# LVDS_BackLight.net
KiCad netlist of a schematic drawn in Altium Designer
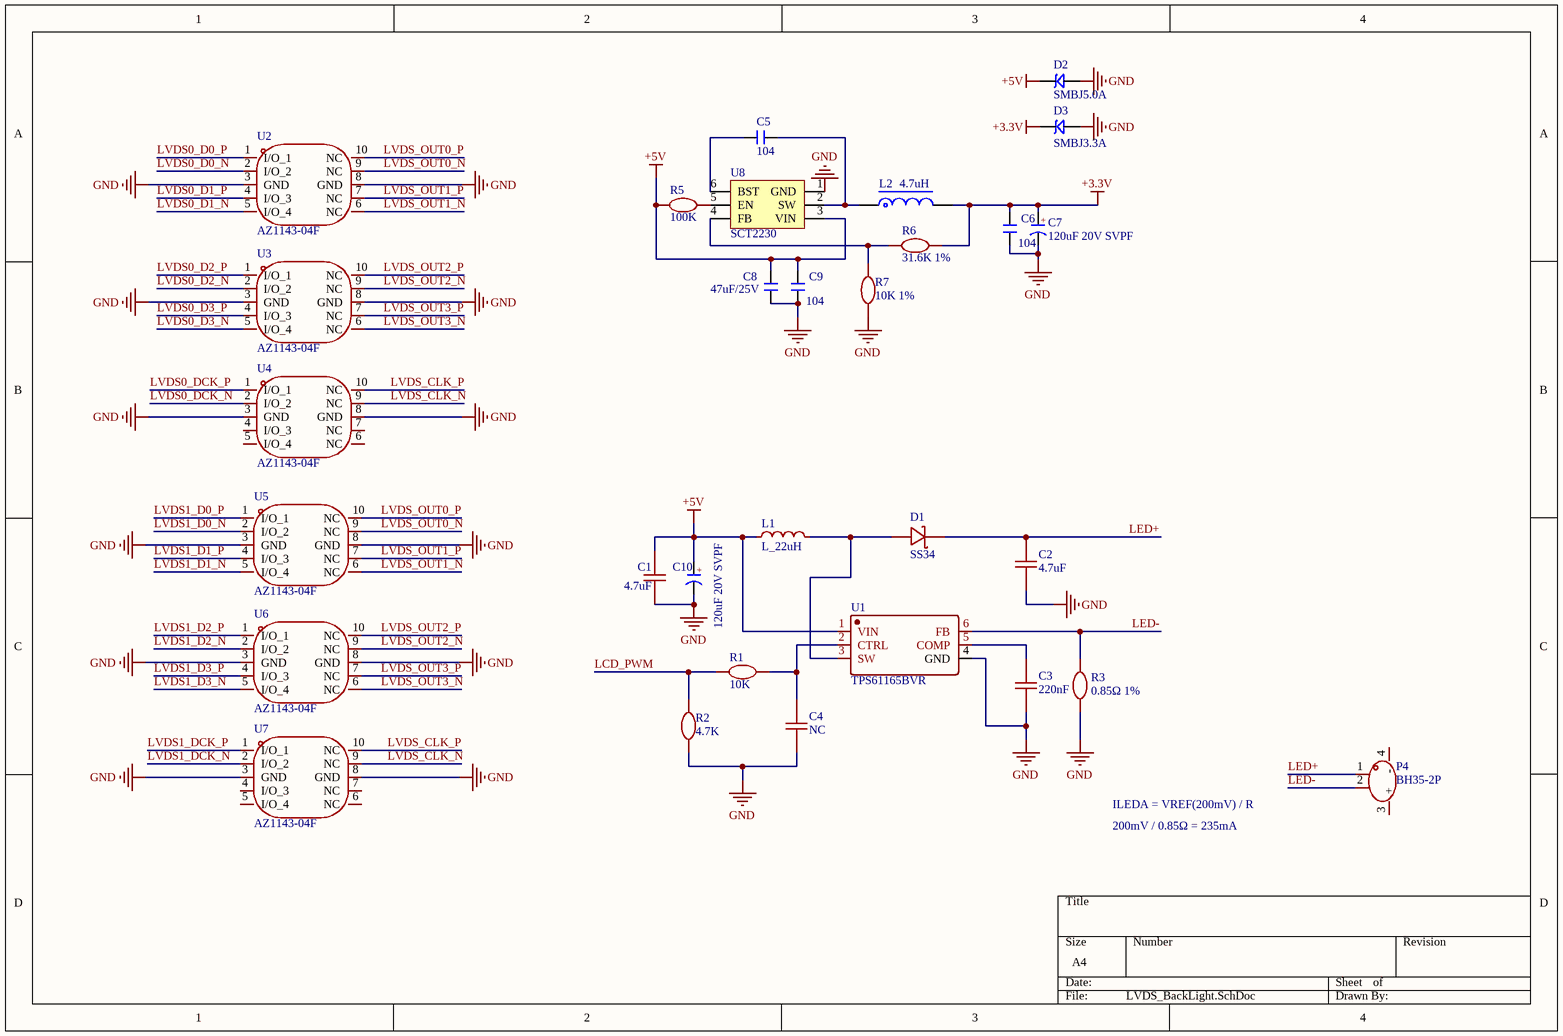
[diagram p0: LVDS_BackLight.SchDoc]

(export (version "E")
  (design (tool "Eeschema 10.0.6"))
  (components
    (comp (ref "C1") (value "4.7uF") (footprint "C0805") (libsource (lib "LVDS_Library") (part "C")))
    (comp (ref "C2") (value "4.7uF") (footprint "C0805") (libsource (lib "LVDS_Library") (part "C")))
    (comp (ref "C3") (value "220nF") (footprint "C0805") (libsource (lib "LVDS_Library") (part "C")))
    (comp (ref "C4") (value "NC") (footprint "C0805") (libsource (lib "LVDS_Library") (part "C")))
    (comp (ref "C5")
      (value "104")
      (footprint "C 0603")
      (description "无极性贴片电容")
      (fields (field (name "版权归属") "源创客"))
      (libsource (lib "ATK_DLRK3568_V1.5") (part "C"))
    )
    (comp (ref "C6")
      (value "104")
      (footprint "C 0603")
      (description "无极性贴片电容")
      (fields (field (name "版权归属") "源创客"))
      (libsource (lib "ATK_DLRK3568_V1.5") (part "C"))
    )
    (comp (ref "C7")
      (value "120uF 20V SVPF")
      (footprint "CM D(6.3*7.7)")
      (description "贴片电解电容")
      (fields (field (name "版权归属") "源创客"))
      (libsource (lib "ATK_DLRK3568_V1.5") (part "C-CM"))
    )
    (comp (ref "C8")
      (value "47uF/25V")
      (footprint "C 1206")
      (description "无极性贴片电容")
      (fields (field (name "版权归属") "源创客"))
      (libsource (lib "ATK_DLRK3568_V1.5") (part "C_1"))
    )
    (comp (ref "C9")
      (value "104")
      (footprint "C 0603")
      (description "无极性贴片电容")
      (fields (field (name "版权归属") "源创客"))
      (libsource (lib "ATK_DLRK3568_V1.5") (part "C"))
    )
    (comp (ref "C10")
      (value "120uF 20V SVPF")
      (footprint "CM D(6.3*7.7)")
      (description "贴片电解电容")
      (fields (field (name "版权归属") "源创客"))
      (libsource (lib "ATK_DLRK3568_V1.5") (part "C-CM"))
    )
    (comp (ref "D1")
      (value "SS34")
      (footprint "SS34_1")
      (description "肖特基二极管")
      (libsource (lib "LVDS_Library") (part "SS34"))
    )
    (comp (ref "D2")
      (value "SMBJ5.0A")
      (footprint "SMBJ")
      (description "TVS")
      (libsource (lib "ATK_DLRK3568_V1.5") (part "SMBJ"))
    )
    (comp (ref "D3")
      (value "SMBJ3.3A")
      (footprint "SMBJ")
      (description "TVS")
      (libsource (lib "ATK_DLRK3568_V1.5") (part "SMBJ_1"))
    )
    (comp (ref "L1") (value "L_22uH") (footprint "L_22uH") (libsource (lib "LVDS_Library") (part "L_22uH")))
    (comp (ref "L2")
      (value "4.7uH")
      (footprint "L-SMD-0420")
      (description "功率屏蔽电感")
      (fields (field (name "版权归属") "源创客"))
      (libsource (lib "ATK_DLRK3568_V1.5") (part "L-CDRH"))
    )
    (comp (ref "P4")
      (value "BH35-2P")
      (footprint "BH35-2P")
      (description "背光插头")
      (libsource (lib "LVDS_Library") (part "BH35-2P"))
    )
    (comp (ref "R1") (value "10K") (footprint "C0805") (libsource (lib "LVDS_Library") (part "R")))
    (comp (ref "R2") (value "4.7K") (footprint "C0805") (libsource (lib "LVDS_Library") (part "R")))
    (comp (ref "R3") (value "0.85Ω 1%") (footprint "C0805") (libsource (lib "LVDS_Library") (part "R")))
    (comp (ref "R5") (value "100K") (footprint "C0805") (libsource (lib "LVDS_Library") (part "R")))
    (comp (ref "R6") (value "31.6K 1%") (footprint "C0805") (libsource (lib "LVDS_Library") (part "R")))
    (comp (ref "R7") (value "10K 1%") (footprint "C0805") (libsource (lib "LVDS_Library") (part "R")))
    (comp (ref "U1")
      (value "TPS61165BVR")
      (footprint "TPS61165BVT")
      (description "TI背光芯片")
      (libsource (lib "LVDS_Library") (part "TPS61165BVR"))
    )
    (comp (ref "U2")
      (value "AZ1143-04F")
      (footprint "AZ1143-04F")
      (description "ESD 保护阵列")
      (libsource (lib "LVDS_Library") (part "AZ1143-04F"))
    )
    (comp (ref "U3")
      (value "AZ1143-04F")
      (footprint "AZ1143-04F")
      (description "ESD 保护阵列")
      (libsource (lib "LVDS_Library") (part "AZ1143-04F"))
    )
    (comp (ref "U4")
      (value "AZ1143-04F")
      (footprint "AZ1143-04F")
      (description "ESD 保护阵列")
      (libsource (lib "LVDS_Library") (part "AZ1143-04F"))
    )
    (comp (ref "U5")
      (value "AZ1143-04F")
      (footprint "AZ1143-04F")
      (description "ESD 保护阵列")
      (libsource (lib "LVDS_Library") (part "AZ1143-04F"))
    )
    (comp (ref "U6")
      (value "AZ1143-04F")
      (footprint "AZ1143-04F")
      (description "ESD 保护阵列")
      (libsource (lib "LVDS_Library") (part "AZ1143-04F"))
    )
    (comp (ref "U7")
      (value "AZ1143-04F")
      (footprint "AZ1143-04F")
      (description "ESD 保护阵列")
      (libsource (lib "LVDS_Library") (part "AZ1143-04F"))
    )
    (comp (ref "U8")
      (value "SCT2230")
      (footprint "SOT23-6N")
      (description "DC降压芯片")
      (libsource (lib "ATK_DLRK3568_V1.5") (part "DC JW5060T_6"))
    )
  )
  (nets
    (net (code "1") (name "+3.3V") (class "Default")
      (node (ref "C6") (pin "2") (pinfunction "2_2") (pintype "passive"))
      (node (ref "C7") (pin "1") (pinfunction "A_1") (pintype "passive"))
      (node (ref "D3") (pin "2") (pintype "passive"))
      (node (ref "L2") (pin "2") (pinfunction "2_2") (pintype "passive"))
      (node (ref "R6") (pin "1") (pinfunction "1_1") (pintype "passive"))
    )
    (net (code "2") (name "+5V") (class "Default")
      (node (ref "C1") (pin "2") (pinfunction "2_2") (pintype "passive"))
      (node (ref "C10") (pin "1") (pinfunction "A_1") (pintype "passive"))
      (node (ref "C8") (pin "2") (pinfunction "2_2") (pintype "passive"))
      (node (ref "C9") (pin "2") (pinfunction "2_2") (pintype "passive"))
      (node (ref "D2") (pin "2") (pintype "passive"))
      (node (ref "L1") (pin "1") (pinfunction "1_1") (pintype "passive"))
      (node (ref "R5") (pin "2") (pinfunction "2_2") (pintype "passive"))
      (node (ref "U1") (pin "1") (pinfunction "VIN_1") (pintype "passive"))
      (node (ref "U8") (pin "3") (pinfunction "VIN_3") (pintype "passive"))
    )
    (net (code "3") (name "/LCD_PWM") (class "Default")
      (node (ref "R1") (pin "2") (pinfunction "2_2") (pintype "passive"))
      (node (ref "R2") (pin "2") (pinfunction "2_2") (pintype "passive"))
    )
    (net (code "4") (name "/LED+") (class "Default")
      (node (ref "C2") (pin "2") (pinfunction "2_2") (pintype "passive"))
      (node (ref "D1") (pin "1") (pinfunction "C_1") (pintype "passive"))
      (node (ref "P4") (pin "1") (pinfunction "1_1") (pintype "passive"))
    )
    (net (code "5") (name "/LED-") (class "Default")
      (node (ref "P4") (pin "2") (pinfunction "2_2") (pintype "passive"))
      (node (ref "R3") (pin "2") (pinfunction "2_2") (pintype "passive"))
      (node (ref "U1") (pin "6") (pinfunction "FB_6") (pintype "passive"))
    )
    (net (code "6") (name "/LVDS0_D0_N") (class "Default")
      (node (ref "U2") (pin "2") (pinfunction "I/O_2_2") (pintype "passive"))
    )
    (net (code "7") (name "/LVDS0_D0_P") (class "Default")
      (node (ref "U2") (pin "1") (pinfunction "I/O_1_1") (pintype "passive"))
    )
    (net (code "8") (name "/LVDS0_D1_N") (class "Default")
      (node (ref "U2") (pin "5") (pinfunction "I/O_4_5") (pintype "passive"))
    )
    (net (code "9") (name "/LVDS0_D1_P") (class "Default")
      (node (ref "U2") (pin "4") (pinfunction "I/O_3_4") (pintype "passive"))
    )
    (net (code "10") (name "/LVDS0_D2_N") (class "Default")
      (node (ref "U3") (pin "2") (pinfunction "I/O_2_2") (pintype "passive"))
    )
    (net (code "11") (name "/LVDS0_D2_P") (class "Default")
      (node (ref "U3") (pin "1") (pinfunction "I/O_1_1") (pintype "passive"))
    )
    (net (code "12") (name "/LVDS0_D3_N") (class "Default")
      (node (ref "U3") (pin "5") (pinfunction "I/O_4_5") (pintype "passive"))
    )
    (net (code "13") (name "/LVDS0_D3_P") (class "Default")
      (node (ref "U3") (pin "4") (pinfunction "I/O_3_4") (pintype "passive"))
    )
    (net (code "14") (name "/LVDS0_DCK_N") (class "Default")
      (node (ref "U4") (pin "2") (pinfunction "I/O_2_2") (pintype "passive"))
    )
    (net (code "15") (name "/LVDS0_DCK_P") (class "Default")
      (node (ref "U4") (pin "1") (pinfunction "I/O_1_1") (pintype "passive"))
    )
    (net (code "16") (name "/LVDS1_D0_N") (class "Default")
      (node (ref "U5") (pin "2") (pinfunction "I/O_2_2") (pintype "passive"))
    )
    (net (code "17") (name "/LVDS1_D0_P") (class "Default")
      (node (ref "U5") (pin "1") (pinfunction "I/O_1_1") (pintype "passive"))
    )
    (net (code "18") (name "/LVDS1_D1_N") (class "Default")
      (node (ref "U5") (pin "5") (pinfunction "I/O_4_5") (pintype "passive"))
    )
    (net (code "19") (name "/LVDS1_D1_P") (class "Default")
      (node (ref "U5") (pin "4") (pinfunction "I/O_3_4") (pintype "passive"))
    )
    (net (code "20") (name "/LVDS1_D2_N") (class "Default")
      (node (ref "U6") (pin "2") (pinfunction "I/O_2_2") (pintype "passive"))
    )
    (net (code "21") (name "/LVDS1_D2_P") (class "Default")
      (node (ref "U6") (pin "1") (pinfunction "I/O_1_1") (pintype "passive"))
    )
    (net (code "22") (name "/LVDS1_D3_N") (class "Default")
      (node (ref "U6") (pin "5") (pinfunction "I/O_4_5") (pintype "passive"))
    )
    (net (code "23") (name "/LVDS1_D3_P") (class "Default")
      (node (ref "U6") (pin "4") (pinfunction "I/O_3_4") (pintype "passive"))
    )
    (net (code "24") (name "/LVDS1_DCK_N") (class "Default")
      (node (ref "U7") (pin "2") (pinfunction "I/O_2_2") (pintype "passive"))
    )
    (net (code "25") (name "/LVDS1_DCK_P") (class "Default")
      (node (ref "U7") (pin "1") (pinfunction "I/O_1_1") (pintype "passive"))
    )
    (net (code "26") (name "/LVDS_CLK_N") (class "Default")
      (node (ref "U4") (pin "9") (pinfunction "NC_9") (pintype "passive"))
      (node (ref "U7") (pin "9") (pinfunction "NC_9") (pintype "passive"))
    )
    (net (code "27") (name "/LVDS_CLK_P") (class "Default")
      (node (ref "U4") (pin "10") (pinfunction "NC_10") (pintype "passive"))
      (node (ref "U7") (pin "10") (pinfunction "NC_10") (pintype "passive"))
    )
    (net (code "28") (name "/LVDS_OUT0_N") (class "Default")
      (node (ref "U2") (pin "9") (pinfunction "NC_9") (pintype "passive"))
      (node (ref "U5") (pin "9") (pinfunction "NC_9") (pintype "passive"))
    )
    (net (code "29") (name "/LVDS_OUT0_P") (class "Default")
      (node (ref "U2") (pin "10") (pinfunction "NC_10") (pintype "passive"))
      (node (ref "U5") (pin "10") (pinfunction "NC_10") (pintype "passive"))
    )
    (net (code "30") (name "/LVDS_OUT1_N") (class "Default")
      (node (ref "U2") (pin "6") (pinfunction "NC_6") (pintype "passive"))
      (node (ref "U5") (pin "6") (pinfunction "NC_6") (pintype "passive"))
    )
    (net (code "31") (name "/LVDS_OUT1_P") (class "Default")
      (node (ref "U2") (pin "7") (pinfunction "NC_7") (pintype "passive"))
      (node (ref "U5") (pin "7") (pinfunction "NC_7") (pintype "passive"))
    )
    (net (code "32") (name "/LVDS_OUT2_N") (class "Default")
      (node (ref "U3") (pin "9") (pinfunction "NC_9") (pintype "passive"))
      (node (ref "U6") (pin "9") (pinfunction "NC_9") (pintype "passive"))
    )
    (net (code "33") (name "/LVDS_OUT2_P") (class "Default")
      (node (ref "U3") (pin "10") (pinfunction "NC_10") (pintype "passive"))
      (node (ref "U6") (pin "10") (pinfunction "NC_10") (pintype "passive"))
    )
    (net (code "34") (name "/LVDS_OUT3_N") (class "Default")
      (node (ref "U3") (pin "6") (pinfunction "NC_6") (pintype "passive"))
      (node (ref "U6") (pin "6") (pinfunction "NC_6") (pintype "passive"))
    )
    (net (code "35") (name "/LVDS_OUT3_P") (class "Default")
      (node (ref "U3") (pin "7") (pinfunction "NC_7") (pintype "passive"))
      (node (ref "U6") (pin "7") (pinfunction "NC_7") (pintype "passive"))
    )
    (net (code "36") (name "GND") (class "Default")
      (node (ref "C1") (pin "1") (pinfunction "1_1") (pintype "passive"))
      (node (ref "C10") (pin "2") (pinfunction "K_2") (pintype "passive"))
      (node (ref "C2") (pin "1") (pinfunction "1_1") (pintype "passive"))
      (node (ref "C3") (pin "1") (pinfunction "1_1") (pintype "passive"))
      (node (ref "C4") (pin "1") (pinfunction "1_1") (pintype "passive"))
      (node (ref "C6") (pin "1") (pinfunction "1_1") (pintype "passive"))
      (node (ref "C7") (pin "2") (pinfunction "K_2") (pintype "passive"))
      (node (ref "C8") (pin "1") (pinfunction "1_1") (pintype "passive"))
      (node (ref "C9") (pin "1") (pinfunction "1_1") (pintype "passive"))
      (node (ref "D2") (pin "1") (pintype "passive"))
      (node (ref "D3") (pin "1") (pintype "passive"))
      (node (ref "R2") (pin "1") (pinfunction "1_1") (pintype "passive"))
      (node (ref "R3") (pin "1") (pinfunction "1_1") (pintype "passive"))
      (node (ref "R7") (pin "2") (pinfunction "2_2") (pintype "passive"))
      (node (ref "U1") (pin "4") (pinfunction "GND_4") (pintype "passive"))
      (node (ref "U2") (pin "3") (pinfunction "GND_3") (pintype "passive"))
      (node (ref "U2") (pin "8") (pinfunction "GND_8") (pintype "passive"))
      (node (ref "U3") (pin "3") (pinfunction "GND_3") (pintype "passive"))
      (node (ref "U3") (pin "8") (pinfunction "GND_8") (pintype "passive"))
      (node (ref "U4") (pin "3") (pinfunction "GND_3") (pintype "passive"))
      (node (ref "U4") (pin "8") (pinfunction "GND_8") (pintype "passive"))
      (node (ref "U5") (pin "3") (pinfunction "GND_3") (pintype "passive"))
      (node (ref "U5") (pin "8") (pinfunction "GND_8") (pintype "passive"))
      (node (ref "U6") (pin "3") (pinfunction "GND_3") (pintype "passive"))
      (node (ref "U6") (pin "8") (pinfunction "GND_8") (pintype "passive"))
      (node (ref "U7") (pin "3") (pinfunction "GND_3") (pintype "passive"))
      (node (ref "U7") (pin "8") (pinfunction "GND_8") (pintype "passive"))
      (node (ref "U8") (pin "1") (pinfunction "GND_1") (pintype "passive"))
    )
    (net (code "37") (name "Net-(D1-A)") (class "Default")
      (node (ref "D1") (pin "2") (pinfunction "A_2") (pintype "passive"))
      (node (ref "L1") (pin "2") (pinfunction "2_2") (pintype "passive"))
      (node (ref "U1") (pin "3") (pinfunction "SW_3") (pintype "passive"))
    )
    (net (code "38") (name "Net-(U1-COMP)") (class "Default")
      (node (ref "C3") (pin "2") (pinfunction "2_2") (pintype "passive"))
      (node (ref "U1") (pin "5") (pinfunction "COMP_5") (pintype "passive"))
    )
    (net (code "39") (name "Net-(U1-CTRL)") (class "Default")
      (node (ref "C4") (pin "2") (pinfunction "2_2") (pintype "passive"))
      (node (ref "R1") (pin "1") (pinfunction "1_1") (pintype "passive"))
      (node (ref "U1") (pin "2") (pinfunction "CTRL_2") (pintype "passive"))
    )
    (net (code "40") (name "Net-(U8-BST)") (class "Default")
      (node (ref "C5") (pin "1") (pinfunction "1_1") (pintype "passive"))
      (node (ref "U8") (pin "6") (pinfunction "BST_6") (pintype "passive"))
    )
    (net (code "41") (name "Net-(U8-EN)") (class "Default")
      (node (ref "R5") (pin "1") (pinfunction "1_1") (pintype "passive"))
      (node (ref "U8") (pin "5") (pinfunction "EN_5") (pintype "passive"))
    )
    (net (code "42") (name "Net-(U8-FB)") (class "Default")
      (node (ref "R6") (pin "2") (pinfunction "2_2") (pintype "passive"))
      (node (ref "R7") (pin "1") (pinfunction "1_1") (pintype "passive"))
      (node (ref "U8") (pin "4") (pinfunction "FB_4") (pintype "passive"))
    )
    (net (code "43") (name "Net-(U8-SW)") (class "Default")
      (node (ref "C5") (pin "2") (pinfunction "2_2") (pintype "passive"))
      (node (ref "L2") (pin "1") (pinfunction "1_1") (pintype "passive"))
      (node (ref "U8") (pin "2") (pinfunction "SW_2") (pintype "passive"))
    )
    (net (code "44") (name "unconnected-(P4-+-Pad3)") (class "Default")
      (node (ref "P4") (pin "3") (pinfunction "+_3") (pintype "passive"))
    )
    (net (code "45") (name "unconnected-(P4---Pad4)") (class "Default")
      (node (ref "P4") (pin "4") (pinfunction "-_4") (pintype "passive"))
    )
    (net (code "46") (name "unconnected-(U4-I{slash}O_3-Pad4)") (class "Default")
      (node (ref "U4") (pin "4") (pinfunction "I/O_3_4") (pintype "passive"))
    )
    (net (code "47") (name "unconnected-(U4-I{slash}O_4-Pad5)") (class "Default")
      (node (ref "U4") (pin "5") (pinfunction "I/O_4_5") (pintype "passive"))
    )
    (net (code "48") (name "unconnected-(U4-NC-Pad6)") (class "Default")
      (node (ref "U4") (pin "6") (pinfunction "NC_6") (pintype "passive"))
    )
    (net (code "49") (name "unconnected-(U4-NC-Pad7)") (class "Default")
      (node (ref "U4") (pin "7") (pinfunction "NC_7") (pintype "passive"))
    )
    (net (code "50") (name "unconnected-(U7-I{slash}O_3-Pad4)") (class "Default")
      (node (ref "U7") (pin "4") (pinfunction "I/O_3_4") (pintype "passive"))
    )
    (net (code "51") (name "unconnected-(U7-I{slash}O_4-Pad5)") (class "Default")
      (node (ref "U7") (pin "5") (pinfunction "I/O_4_5") (pintype "passive"))
    )
    (net (code "52") (name "unconnected-(U7-NC-Pad6)") (class "Default")
      (node (ref "U7") (pin "6") (pinfunction "NC_6") (pintype "passive"))
    )
    (net (code "53") (name "unconnected-(U7-NC-Pad7)") (class "Default")
      (node (ref "U7") (pin "7") (pinfunction "NC_7") (pintype "passive"))
    )
  )
)
